# mcu0_primary.net
KiCad netlist of a schematic drawn in Altium Designer
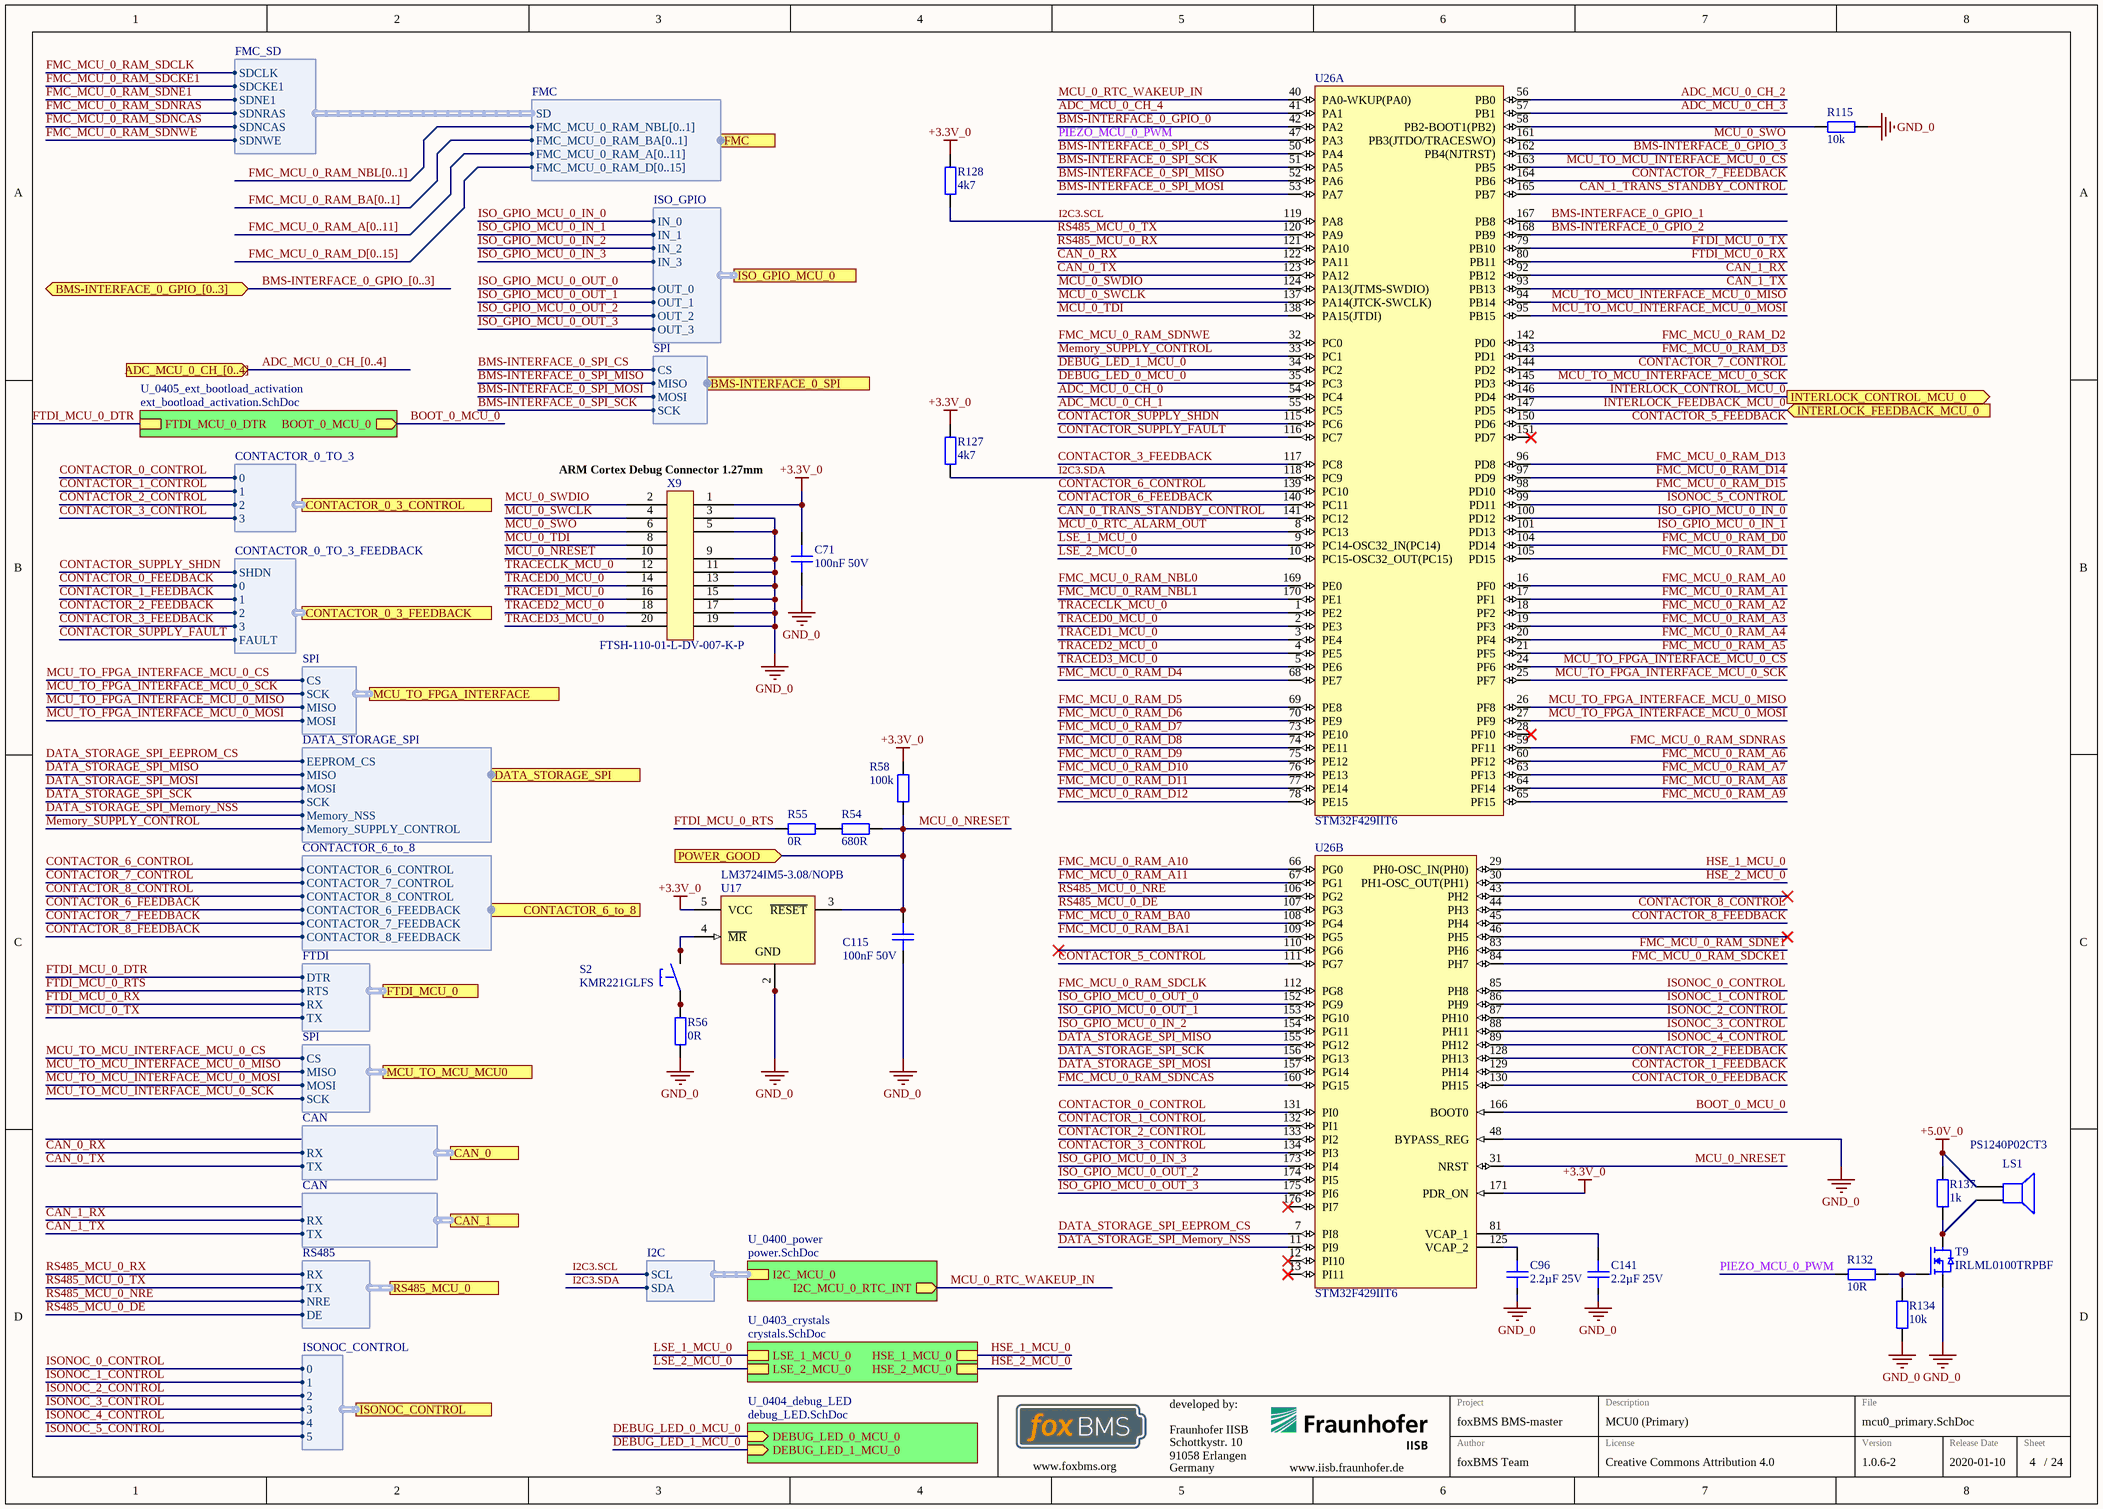
[diagram p0: mcu0_primary.SchDoc]

(export (version "E")
  (design (tool "Eeschema 10.0.6"))
  (components
    (comp (ref "C71")
      (value "100nF 50V")
      (footprint "0603C")
      (description "Ceramic, 100nF, ±10%, 50V, X7R, –55 to 125°C, 0603 (1608),RoHS, Automotive")
      (fields (field (name "PART NUMBER") "GCJ188R71H104KA12") (field (name "TOLERANCE") "±10%"))
      (libsource (lib "master-010106") (part "C"))
    )
    (comp (ref "C96")
      (value "2.2µF 25V")
      (footprint "0805C")
      (description "Ceramic, 2.2µF, ±10%, 25V, X7R, –55 to 125°C, 0805 (2012),RoHS, Automotive")
      (fields (field (name "PART NUMBER") "GCJ21BR71E225KA01") (field (name "TOLERANCE") "±10%"))
      (libsource (lib "master-010106") (part "gen_C_ceramic_2u2_50V_X7R_0805"))
    )
    (comp (ref "C115")
      (value "100nF 50V")
      (footprint "0603C")
      (description "Ceramic, 100nF, ±10%, 50V, X7R, –55 to 125°C, 0603 (1608),RoHS, Automotive")
      (fields (field (name "PART NUMBER") "GCJ188R71H104KA12") (field (name "TOLERANCE") "±10%"))
      (libsource (lib "master-010106") (part "C"))
    )
    (comp (ref "C141")
      (value "2.2µF 25V")
      (footprint "0805C")
      (description "Ceramic, 2.2µF, ±10%, 25V, X7R, –55 to 125°C, 0805 (2012),RoHS, Automotive")
      (fields (field (name "PART NUMBER") "GCJ21BR71E225KA01") (field (name "TOLERANCE") "±10%"))
      (libsource (lib "master-010106") (part "gen_C_ceramic_2u2_50V_X7R_0805"))
    )
    (comp (ref "LS1")
      (value "PS1240P02CT3")
      (footprint "PS12")
      (description "Loudspeaker")
      (libsource (lib "Miscellaneous Devices") (part "Speaker"))
    )
    (comp (ref "R54")
      (value "680R")
      (footprint "0603R")
      (description "SMD Resistor 680R 0603")
      (fields (field (name "PART NUMBER") "gen_R_680R_0603") (field (name "TOLERANCE") "1%"))
      (libsource (lib "master-010106") (part "R"))
    )
    (comp (ref "R55")
      (value "0R")
      (footprint "0603R")
      (description "SMD Resistor 0R 0603")
      (fields (field (name "PART NUMBER") "gen_R_0R_0603") (field (name "POWER") "0.1W"))
      (libsource (lib "master-010106") (part "R"))
    )
    (comp (ref "R56")
      (value "0R")
      (footprint "0603R")
      (description "SMD Resistor 0R 0603")
      (fields (field (name "PART NUMBER") "gen_R_0R_0603") (field (name "POWER") "0.1W"))
      (libsource (lib "master-010106") (part "R"))
    )
    (comp (ref "R58")
      (value "100k")
      (footprint "0603R")
      (description "SMD Resistor 100k 0603")
      (fields (field (name "PART NUMBER") "gen_R_100k_0603"))
      (libsource (lib "master-010106") (part "gen_R_100k_0603"))
    )
    (comp (ref "R115")
      (value "10k")
      (footprint "0603R")
      (description "SMD Resistor 10k 0603")
      (fields (field (name "PART NUMBER") "gen_R_10k_0603") (field (name "TOLERANCE") "1%"))
      (libsource (lib "master-010106") (part "R"))
    )
    (comp (ref "R127")
      (value "4k7")
      (footprint "0603R")
      (description "SMD Resistor 4.7k 0603")
      (fields (field (name "PART NUMBER") "gen_R_4k7_0603"))
      (libsource (lib "master-010106") (part "gen_R_4k7_0603"))
    )
    (comp (ref "R128")
      (value "4k7")
      (footprint "0603R")
      (description "SMD Resistor 4.7k 0603")
      (fields (field (name "PART NUMBER") "gen_R_4k7_0603"))
      (libsource (lib "master-010106") (part "gen_R_4k7_0603"))
    )
    (comp (ref "R132")
      (value "10R")
      (footprint "0603R")
      (description "SMD Resistor 10R 0603")
      (fields (field (name "PART NUMBER") "gen_R_10R_0603") (field (name "TOLERANCE") "1%"))
      (libsource (lib "master-010106") (part "R"))
    )
    (comp (ref "R134")
      (value "10k")
      (footprint "0603R")
      (description "SMD Resistor 10k 0603")
      (fields (field (name "PART NUMBER") "gen_R_10k_0603") (field (name "TOLERANCE") "1%"))
      (libsource (lib "master-010106") (part "R"))
    )
    (comp (ref "R137")
      (value "1k")
      (footprint "0603R")
      (description "SMD Resistor 1k 0603")
      (fields (field (name "PART NUMBER") "gen_R_1k_0603") (field (name "TOLERANCE") "1%"))
      (libsource (lib "master-010106") (part "R"))
    )
    (comp (ref "S2")
      (value "KMR221GLFS")
      (footprint "KMR2_Series")
      (description "Microminiature Tactile Switch")
      (fields (field (name "MANUFACTURER") "CK Components"))
      (libsource (lib "OE750") (part "Switch_4_Pin"))
    )
    (comp (ref "T9")
      (value "IRLML0100TRPBF")
      (footprint "SOT95P237X110-3N")
      (description "MOSFET-Transistor, n-Kanal, 1.6 A, 100 V, 0.178 ohm, 10 V, 2.5 V")
      (fields (field (name "MANUFACTURER") "Infineon"))
      (libsource (lib "OE750") (part "NMOS"))
    )
    (comp (ref "U17")
      (value "LM3724IM5-3.08/NOPB")
      (footprint "MF05A_N")
      (description "5-Pin Microprocessor Reset Circuits, 5-pin SOT-23, Pb-Free")
      (fields (field (name "MANUFACTURER") "National Semiconductor"))
      (libsource (lib "Altium Content Vault") (part "PM-SCCT-LM3724-5"))
    )
    (comp (ref "U26")
      (value "STM32F429IIT6")
      (footprint "STM-LQFP176_N")
      (fields (field (name "MANUFACTURER") "STMicroelectronics"))
      (libsource (lib "ti-import") (part "MC-ARM-STM32F4X9-SQ176"))
    )
    (comp (ref "X9")
      (value "FTSH-110-01-L-DV-007-K-P")
      (footprint "CORTEX_DEBUG_20_PIN")
      (description "Board-To-Board Connector, ARM Cortex Debug Header 20 Pin")
      (fields
        (field (name "PART NUMBER") "samtec_FTSH-110-01-L-DV-007-K-P")
        (field (name "MANUFACTURER") "Samtec")
      )
      (libsource (lib "OE750") (part "CORTEX_DEBUG_20_PIN"))
    )
  )
  (nets
    (net (code "14") (name "+3.3V_0") (class "Default")
      (node (ref "C71") (pin "1") (pinfunction "1_1") (pintype "passive"))
      (node (ref "R127") (pin "2") (pinfunction "2_2") (pintype "passive"))
      (node (ref "R128") (pin "2") (pinfunction "2_2") (pintype "passive"))
      (node (ref "R58") (pin "2") (pinfunction "2_2") (pintype "passive"))
      (node (ref "U17") (pin "5") (pinfunction "VCC_5") (pintype "power_in"))
      (node (ref "U26") (pin "171") (pinfunction "PDR_ON_171") (pintype "input"))
      (node (ref "X9") (pin "1") (pintype "passive"))
    )
    (net (code "15") (name "+5.0V_0") (class "Default")
      (node (ref "LS1") (pin "1") (pinfunction "1_1") (pintype "passive"))
      (node (ref "R137") (pin "2") (pinfunction "2_2") (pintype "passive"))
    )
    (net (code "16") (name "/ADC_MCU_0_CH_0") (class "Default")
      (node (ref "U26") (pin "54") (pinfunction "PC4_54") (pintype "bidirectional"))
    )
    (net (code "17") (name "/ADC_MCU_0_CH_1") (class "Default")
      (node (ref "U26") (pin "55") (pinfunction "PC5_55") (pintype "bidirectional"))
    )
    (net (code "18") (name "/ADC_MCU_0_CH_2") (class "Default")
      (node (ref "U26") (pin "56") (pinfunction "PB0_56") (pintype "bidirectional"))
    )
    (net (code "19") (name "/ADC_MCU_0_CH_3") (class "Default")
      (node (ref "U26") (pin "57") (pinfunction "PB1_57") (pintype "bidirectional"))
    )
    (net (code "20") (name "/ADC_MCU_0_CH_4") (class "Default")
      (node (ref "U26") (pin "41") (pinfunction "PA1_41") (pintype "bidirectional"))
    )
    (net (code "22") (name "/BMS-INTERFACE_0_GPIO_0") (class "Default")
      (node (ref "U26") (pin "42") (pinfunction "PA2_42") (pintype "bidirectional"))
    )
    (net (code "23") (name "/BMS-INTERFACE_0_GPIO_1") (class "Default")
      (node (ref "U26") (pin "167") (pinfunction "PB8_167") (pintype "bidirectional"))
    )
    (net (code "24") (name "/BMS-INTERFACE_0_GPIO_2") (class "Default")
      (node (ref "U26") (pin "168") (pinfunction "PB9_168") (pintype "bidirectional"))
    )
    (net (code "25") (name "/BMS-INTERFACE_0_GPIO_3") (class "Default")
      (node (ref "U26") (pin "162") (pinfunction "PB4(NJTRST)_162") (pintype "bidirectional"))
    )
    (net (code "27") (name "/BMS-INTERFACE_0_SPI_CS") (class "Default")
      (node (ref "U26") (pin "50") (pinfunction "PA4_50") (pintype "bidirectional"))
    )
    (net (code "28") (name "/BMS-INTERFACE_0_SPI_MISO") (class "Default")
      (node (ref "U26") (pin "52") (pinfunction "PA6_52") (pintype "bidirectional"))
    )
    (net (code "29") (name "/BMS-INTERFACE_0_SPI_MOSI") (class "Default")
      (node (ref "U26") (pin "53") (pinfunction "PA7_53") (pintype "bidirectional"))
    )
    (net (code "30") (name "/BMS-INTERFACE_0_SPI_SCK") (class "Default")
      (node (ref "U26") (pin "51") (pinfunction "PA5_51") (pintype "bidirectional"))
    )
    (net (code "31") (name "/BOOT_0_MCU_0") (class "Default")
      (node (ref "U26") (pin "166") (pinfunction "BOOT0_166") (pintype "input"))
    )
    (net (code "32") (name "/CAN_0_RX") (class "Default")
      (node (ref "U26") (pin "122") (pinfunction "PA11_122") (pintype "bidirectional"))
    )
    (net (code "33") (name "/CAN_0_TRANS_STANDBY_CONTROL") (class "Default")
      (node (ref "U26") (pin "141") (pinfunction "PC12_141") (pintype "bidirectional"))
    )
    (net (code "34") (name "/CAN_0_TX") (class "Default")
      (node (ref "U26") (pin "123") (pinfunction "PA12_123") (pintype "bidirectional"))
    )
    (net (code "35") (name "/CAN_1_RX") (class "Default")
      (node (ref "U26") (pin "92") (pinfunction "PB12_92") (pintype "bidirectional"))
    )
    (net (code "36") (name "/CAN_1_TRANS_STANDBY_CONTROL") (class "Default")
      (node (ref "U26") (pin "165") (pinfunction "PB7_165") (pintype "bidirectional"))
    )
    (net (code "37") (name "/CAN_1_TX") (class "Default")
      (node (ref "U26") (pin "93") (pinfunction "PB13_93") (pintype "bidirectional"))
    )
    (net (code "38") (name "/CONTACTOR_0_CONTROL") (class "Default")
      (node (ref "U26") (pin "131") (pinfunction "PI0_131") (pintype "bidirectional"))
    )
    (net (code "39") (name "/CONTACTOR_0_FEEDBACK") (class "Default")
      (node (ref "U26") (pin "130") (pinfunction "PH15_130") (pintype "bidirectional"))
    )
    (net (code "40") (name "/CONTACTOR_1_CONTROL") (class "Default")
      (node (ref "U26") (pin "132") (pinfunction "PI1_132") (pintype "bidirectional"))
    )
    (net (code "41") (name "/CONTACTOR_1_FEEDBACK") (class "Default")
      (node (ref "U26") (pin "129") (pinfunction "PH14_129") (pintype "bidirectional"))
    )
    (net (code "42") (name "/CONTACTOR_2_CONTROL") (class "Default")
      (node (ref "U26") (pin "133") (pinfunction "PI2_133") (pintype "bidirectional"))
    )
    (net (code "43") (name "/CONTACTOR_2_FEEDBACK") (class "Default")
      (node (ref "U26") (pin "128") (pinfunction "PH13_128") (pintype "bidirectional"))
    )
    (net (code "44") (name "/CONTACTOR_3_CONTROL") (class "Default")
      (node (ref "U26") (pin "134") (pinfunction "PI3_134") (pintype "bidirectional"))
    )
    (net (code "45") (name "/CONTACTOR_3_FEEDBACK") (class "Default")
      (node (ref "U26") (pin "117") (pinfunction "PC8_117") (pintype "bidirectional"))
    )
    (net (code "46") (name "/CONTACTOR_5_CONTROL") (class "Default")
      (node (ref "U26") (pin "111") (pinfunction "PG7_111") (pintype "bidirectional"))
    )
    (net (code "47") (name "/CONTACTOR_5_FEEDBACK") (class "Default")
      (node (ref "U26") (pin "150") (pinfunction "PD6_150") (pintype "bidirectional"))
    )
    (net (code "48") (name "/CONTACTOR_6_CONTROL") (class "Default")
      (node (ref "U26") (pin "139") (pinfunction "PC10_139") (pintype "bidirectional"))
    )
    (net (code "49") (name "/CONTACTOR_6_FEEDBACK") (class "Default")
      (node (ref "U26") (pin "140") (pinfunction "PC11_140") (pintype "bidirectional"))
    )
    (net (code "50") (name "/CONTACTOR_7_CONTROL") (class "Default")
      (node (ref "U26") (pin "144") (pinfunction "PD2_144") (pintype "bidirectional"))
    )
    (net (code "51") (name "/CONTACTOR_7_FEEDBACK") (class "Default")
      (node (ref "U26") (pin "164") (pinfunction "PB6_164") (pintype "bidirectional"))
    )
    (net (code "52") (name "/CONTACTOR_8_CONTROL") (class "Default")
      (node (ref "U26") (pin "44") (pinfunction "PH3_44") (pintype "bidirectional"))
    )
    (net (code "53") (name "/CONTACTOR_8_FEEDBACK") (class "Default")
      (node (ref "U26") (pin "45") (pinfunction "PH4_45") (pintype "bidirectional"))
    )
    (net (code "54") (name "/CONTACTOR_SUPPLY_FAULT") (class "Default")
      (node (ref "U26") (pin "116") (pinfunction "PC7_116") (pintype "bidirectional"))
    )
    (net (code "55") (name "/CONTACTOR_SUPPLY_SHDN") (class "Default")
      (node (ref "U26") (pin "115") (pinfunction "PC6_115") (pintype "bidirectional"))
    )
    (net (code "56") (name "/DATA_STORAGE_SPI_EEPROM_CS") (class "Default")
      (node (ref "U26") (pin "7") (pinfunction "PI8_7") (pintype "bidirectional"))
    )
    (net (code "57") (name "/DATA_STORAGE_SPI_MISO") (class "Default")
      (node (ref "U26") (pin "155") (pinfunction "PG12_155") (pintype "bidirectional"))
    )
    (net (code "58") (name "/DATA_STORAGE_SPI_MOSI") (class "Default")
      (node (ref "U26") (pin "157") (pinfunction "PG14_157") (pintype "bidirectional"))
    )
    (net (code "59") (name "/DATA_STORAGE_SPI_Memory_NSS") (class "Default")
      (node (ref "U26") (pin "11") (pinfunction "PI9_11") (pintype "bidirectional"))
    )
    (net (code "60") (name "/DATA_STORAGE_SPI_SCK") (class "Default")
      (node (ref "U26") (pin "156") (pinfunction "PG13_156") (pintype "bidirectional"))
    )
    (net (code "61") (name "/DEBUG_LED_0_MCU_0") (class "Default")
      (node (ref "U26") (pin "35") (pinfunction "PC3_35") (pintype "bidirectional"))
    )
    (net (code "62") (name "/DEBUG_LED_1_MCU_0") (class "Default")
      (node (ref "U26") (pin "34") (pinfunction "PC2_34") (pintype "bidirectional"))
    )
    (net (code "63") (name "/FMC_MCU_0_RAM_A0") (class "Default")
      (node (ref "U26") (pin "16") (pinfunction "PF0_16") (pintype "bidirectional"))
    )
    (net (code "64") (name "/FMC_MCU_0_RAM_A1") (class "Default")
      (node (ref "U26") (pin "17") (pinfunction "PF1_17") (pintype "bidirectional"))
    )
    (net (code "65") (name "/FMC_MCU_0_RAM_A2") (class "Default")
      (node (ref "U26") (pin "18") (pinfunction "PF2_18") (pintype "bidirectional"))
    )
    (net (code "66") (name "/FMC_MCU_0_RAM_A3") (class "Default")
      (node (ref "U26") (pin "19") (pinfunction "PF3_19") (pintype "bidirectional"))
    )
    (net (code "67") (name "/FMC_MCU_0_RAM_A4") (class "Default")
      (node (ref "U26") (pin "20") (pinfunction "PF4_20") (pintype "bidirectional"))
    )
    (net (code "68") (name "/FMC_MCU_0_RAM_A5") (class "Default")
      (node (ref "U26") (pin "21") (pinfunction "PF5_21") (pintype "bidirectional"))
    )
    (net (code "69") (name "/FMC_MCU_0_RAM_A6") (class "Default")
      (node (ref "U26") (pin "60") (pinfunction "PF12_60") (pintype "bidirectional"))
    )
    (net (code "70") (name "/FMC_MCU_0_RAM_A7") (class "Default")
      (node (ref "U26") (pin "63") (pinfunction "PF13_63") (pintype "bidirectional"))
    )
    (net (code "71") (name "/FMC_MCU_0_RAM_A8") (class "Default")
      (node (ref "U26") (pin "64") (pinfunction "PF14_64") (pintype "bidirectional"))
    )
    (net (code "72") (name "/FMC_MCU_0_RAM_A9") (class "Default")
      (node (ref "U26") (pin "65") (pinfunction "PF15_65") (pintype "bidirectional"))
    )
    (net (code "73") (name "/FMC_MCU_0_RAM_A10") (class "Default")
      (node (ref "U26") (pin "66") (pinfunction "PG0_66") (pintype "bidirectional"))
    )
    (net (code "74") (name "/FMC_MCU_0_RAM_A11") (class "Default")
      (node (ref "U26") (pin "67") (pinfunction "PG1_67") (pintype "bidirectional"))
    )
    (net (code "76") (name "/FMC_MCU_0_RAM_BA0") (class "Default")
      (node (ref "U26") (pin "108") (pinfunction "PG4_108") (pintype "bidirectional"))
    )
    (net (code "77") (name "/FMC_MCU_0_RAM_BA1") (class "Default")
      (node (ref "U26") (pin "109") (pinfunction "PG5_109") (pintype "bidirectional"))
    )
    (net (code "79") (name "/FMC_MCU_0_RAM_D0") (class "Default")
      (node (ref "U26") (pin "104") (pinfunction "PD14_104") (pintype "bidirectional"))
    )
    (net (code "80") (name "/FMC_MCU_0_RAM_D1") (class "Default")
      (node (ref "U26") (pin "105") (pinfunction "PD15_105") (pintype "bidirectional"))
    )
    (net (code "81") (name "/FMC_MCU_0_RAM_D2") (class "Default")
      (node (ref "U26") (pin "142") (pinfunction "PD0_142") (pintype "bidirectional"))
    )
    (net (code "82") (name "/FMC_MCU_0_RAM_D3") (class "Default")
      (node (ref "U26") (pin "143") (pinfunction "PD1_143") (pintype "bidirectional"))
    )
    (net (code "83") (name "/FMC_MCU_0_RAM_D4") (class "Default")
      (node (ref "U26") (pin "68") (pinfunction "PE7_68") (pintype "bidirectional"))
    )
    (net (code "84") (name "/FMC_MCU_0_RAM_D5") (class "Default")
      (node (ref "U26") (pin "69") (pinfunction "PE8_69") (pintype "bidirectional"))
    )
    (net (code "85") (name "/FMC_MCU_0_RAM_D6") (class "Default")
      (node (ref "U26") (pin "70") (pinfunction "PE9_70") (pintype "bidirectional"))
    )
    (net (code "86") (name "/FMC_MCU_0_RAM_D7") (class "Default")
      (node (ref "U26") (pin "73") (pinfunction "PE10_73") (pintype "bidirectional"))
    )
    (net (code "87") (name "/FMC_MCU_0_RAM_D8") (class "Default")
      (node (ref "U26") (pin "74") (pinfunction "PE11_74") (pintype "bidirectional"))
    )
    (net (code "88") (name "/FMC_MCU_0_RAM_D9") (class "Default")
      (node (ref "U26") (pin "75") (pinfunction "PE12_75") (pintype "bidirectional"))
    )
    (net (code "89") (name "/FMC_MCU_0_RAM_D10") (class "Default")
      (node (ref "U26") (pin "76") (pinfunction "PE13_76") (pintype "bidirectional"))
    )
    (net (code "90") (name "/FMC_MCU_0_RAM_D11") (class "Default")
      (node (ref "U26") (pin "77") (pinfunction "PE14_77") (pintype "bidirectional"))
    )
    (net (code "91") (name "/FMC_MCU_0_RAM_D12") (class "Default")
      (node (ref "U26") (pin "78") (pinfunction "PE15_78") (pintype "bidirectional"))
    )
    (net (code "92") (name "/FMC_MCU_0_RAM_D13") (class "Default")
      (node (ref "U26") (pin "96") (pinfunction "PD8_96") (pintype "bidirectional"))
    )
    (net (code "93") (name "/FMC_MCU_0_RAM_D14") (class "Default")
      (node (ref "U26") (pin "97") (pinfunction "PD9_97") (pintype "bidirectional"))
    )
    (net (code "94") (name "/FMC_MCU_0_RAM_D15") (class "Default")
      (node (ref "U26") (pin "98") (pinfunction "PD10_98") (pintype "bidirectional"))
    )
    (net (code "96") (name "/FMC_MCU_0_RAM_NBL0") (class "Default")
      (node (ref "U26") (pin "169") (pinfunction "PE0_169") (pintype "bidirectional"))
    )
    (net (code "97") (name "/FMC_MCU_0_RAM_NBL1") (class "Default")
      (node (ref "U26") (pin "170") (pinfunction "PE1_170") (pintype "bidirectional"))
    )
    (net (code "99") (name "/FMC_MCU_0_RAM_SDCKE1") (class "Default")
      (node (ref "U26") (pin "84") (pinfunction "PH7_84") (pintype "bidirectional"))
    )
    (net (code "100") (name "/FMC_MCU_0_RAM_SDCLK") (class "Default")
      (node (ref "U26") (pin "112") (pinfunction "PG8_112") (pintype "bidirectional"))
    )
    (net (code "101") (name "/FMC_MCU_0_RAM_SDNCAS") (class "Default")
      (node (ref "U26") (pin "160") (pinfunction "PG15_160") (pintype "bidirectional"))
    )
    (net (code "102") (name "/FMC_MCU_0_RAM_SDNE1") (class "Default")
      (node (ref "U26") (pin "83") (pinfunction "PH6_83") (pintype "bidirectional"))
    )
    (net (code "103") (name "/FMC_MCU_0_RAM_SDNRAS") (class "Default")
      (node (ref "U26") (pin "59") (pinfunction "PF11_59") (pintype "bidirectional"))
    )
    (net (code "104") (name "/FMC_MCU_0_RAM_SDNWE") (class "Default")
      (node (ref "U26") (pin "32") (pinfunction "PC0_32") (pintype "bidirectional"))
    )
    (net (code "107") (name "/FTDI_MCU_0_RTS") (class "Default")
      (node (ref "R55") (pin "2") (pinfunction "2_2") (pintype "passive"))
    )
    (net (code "108") (name "/FTDI_MCU_0_RX") (class "Default")
      (node (ref "U26") (pin "80") (pinfunction "PB11_80") (pintype "bidirectional"))
    )
    (net (code "109") (name "/FTDI_MCU_0_TX") (class "Default")
      (node (ref "U26") (pin "79") (pinfunction "PB10_79") (pintype "bidirectional"))
    )
    (net (code "110") (name "/HSE_1_MCU_0") (class "Default")
      (node (ref "U26") (pin "29") (pinfunction "PH0-OSC_IN(PH0)_29") (pintype "bidirectional"))
    )
    (net (code "111") (name "/HSE_2_MCU_0") (class "Default")
      (node (ref "U26") (pin "30") (pinfunction "PH1-OSC_OUT(PH1)_30") (pintype "bidirectional"))
    )
    (net (code "112") (name "/I2C3.SCL") (class "Default")
      (node (ref "R128") (pin "1") (pinfunction "1_1") (pintype "passive"))
      (node (ref "U26") (pin "119") (pinfunction "PA8_119") (pintype "bidirectional"))
    )
    (net (code "113") (name "/I2C3.SDA") (class "Default")
      (node (ref "R127") (pin "1") (pinfunction "1_1") (pintype "passive"))
      (node (ref "U26") (pin "118") (pinfunction "PC9_118") (pintype "bidirectional"))
    )
    (net (code "114") (name "/INTERLOCK_CONTROL_MCU_0") (class "Default")
      (node (ref "U26") (pin "146") (pinfunction "PD4_146") (pintype "bidirectional"))
    )
    (net (code "115") (name "/INTERLOCK_FEEDBACK_MCU_0") (class "Default")
      (node (ref "U26") (pin "147") (pinfunction "PD5_147") (pintype "bidirectional"))
    )
    (net (code "116") (name "/ISONOC_0_CONTROL") (class "Default")
      (node (ref "U26") (pin "85") (pinfunction "PH8_85") (pintype "bidirectional"))
    )
    (net (code "117") (name "/ISONOC_1_CONTROL") (class "Default")
      (node (ref "U26") (pin "86") (pinfunction "PH9_86") (pintype "bidirectional"))
    )
    (net (code "118") (name "/ISONOC_2_CONTROL") (class "Default")
      (node (ref "U26") (pin "87") (pinfunction "PH10_87") (pintype "bidirectional"))
    )
    (net (code "119") (name "/ISONOC_3_CONTROL") (class "Default")
      (node (ref "U26") (pin "88") (pinfunction "PH11_88") (pintype "bidirectional"))
    )
    (net (code "120") (name "/ISONOC_4_CONTROL") (class "Default")
      (node (ref "U26") (pin "89") (pinfunction "PH12_89") (pintype "bidirectional"))
    )
    (net (code "121") (name "/ISONOC_5_CONTROL") (class "Default")
      (node (ref "U26") (pin "99") (pinfunction "PD11_99") (pintype "bidirectional"))
    )
    (net (code "122") (name "/ISO_GPIO_MCU_0_IN_0") (class "Default")
      (node (ref "U26") (pin "100") (pinfunction "PD12_100") (pintype "bidirectional"))
    )
    (net (code "123") (name "/ISO_GPIO_MCU_0_IN_1") (class "Default")
      (node (ref "U26") (pin "101") (pinfunction "PD13_101") (pintype "bidirectional"))
    )
    (net (code "124") (name "/ISO_GPIO_MCU_0_IN_2") (class "Default")
      (node (ref "U26") (pin "154") (pinfunction "PG11_154") (pintype "bidirectional"))
    )
    (net (code "125") (name "/ISO_GPIO_MCU_0_IN_3") (class "Default")
      (node (ref "U26") (pin "173") (pinfunction "PI4_173") (pintype "bidirectional"))
    )
    (net (code "126") (name "/ISO_GPIO_MCU_0_OUT_0") (class "Default")
      (node (ref "U26") (pin "152") (pinfunction "PG9_152") (pintype "bidirectional"))
    )
    (net (code "127") (name "/ISO_GPIO_MCU_0_OUT_1") (class "Default")
      (node (ref "U26") (pin "153") (pinfunction "PG10_153") (pintype "bidirectional"))
    )
    (net (code "128") (name "/ISO_GPIO_MCU_0_OUT_2") (class "Default")
      (node (ref "U26") (pin "174") (pinfunction "PI5_174") (pintype "bidirectional"))
    )
    (net (code "129") (name "/ISO_GPIO_MCU_0_OUT_3") (class "Default")
      (node (ref "U26") (pin "175") (pinfunction "PI6_175") (pintype "bidirectional"))
    )
    (net (code "130") (name "/LSE_1_MCU_0") (class "Default")
      (node (ref "U26") (pin "9") (pinfunction "PC14-OSC32_IN(PC14)_9") (pintype "bidirectional"))
    )
    (net (code "131") (name "/LSE_2_MCU_0") (class "Default")
      (node (ref "U26") (pin "10") (pinfunction "PC15-OSC32_OUT(PC15)_10") (pintype "bidirectional"))
    )
    (net (code "132") (name "/MCU_0_NRESET") (class "Default")
      (node (ref "C115") (pin "1") (pinfunction "1_1") (pintype "passive"))
      (node (ref "R54") (pin "1") (pinfunction "1_1") (pintype "passive"))
      (node (ref "R58") (pin "1") (pinfunction "1_1") (pintype "passive"))
      (node (ref "U17") (pin "3") (pinfunction "~{RESET}_3") (pintype "open_collector"))
      (node (ref "U26") (pin "31") (pinfunction "NRST_31") (pintype "bidirectional"))
      (node (ref "X9") (pin "10") (pintype "passive"))
    )
    (net (code "133") (name "/MCU_0_RTC_ALARM_OUT") (class "Default")
      (node (ref "U26") (pin "8") (pinfunction "PC13_8") (pintype "bidirectional"))
    )
    (net (code "134") (name "/MCU_0_RTC_WAKEUP_IN") (class "Default")
      (node (ref "U26") (pin "40") (pinfunction "PA0-WKUP(PA0)_40") (pintype "bidirectional"))
    )
    (net (code "135") (name "/MCU_0_SWCLK") (class "Default")
      (node (ref "U26") (pin "137") (pinfunction "PA14(JTCK-SWCLK)_137") (pintype "bidirectional"))
      (node (ref "X9") (pin "4") (pintype "passive"))
    )
    (net (code "136") (name "/MCU_0_SWDIO") (class "Default")
      (node (ref "U26") (pin "124") (pinfunction "PA13(JTMS-SWDIO)_124") (pintype "bidirectional"))
      (node (ref "X9") (pin "2") (pintype "passive"))
    )
    (net (code "137") (name "/MCU_0_SWO") (class "Default")
      (node (ref "U26") (pin "161") (pinfunction "PB3(JTDO/TRACESWO)_161") (pintype "bidirectional"))
      (node (ref "X9") (pin "6") (pintype "passive"))
    )
    (net (code "138") (name "/MCU_0_TDI") (class "Default")
      (node (ref "U26") (pin "138") (pinfunction "PA15(JTDI)_138") (pintype "bidirectional"))
      (node (ref "X9") (pin "8") (pintype "passive"))
    )
    (net (code "139") (name "/MCU_TO_FPGA_INTERFACE_MCU_0_CS") (class "Default")
      (node (ref "U26") (pin "24") (pinfunction "PF6_24") (pintype "bidirectional"))
    )
    (net (code "140") (name "/MCU_TO_FPGA_INTERFACE_MCU_0_MISO") (class "Default")
      (node (ref "U26") (pin "26") (pinfunction "PF8_26") (pintype "bidirectional"))
    )
    (net (code "141") (name "/MCU_TO_FPGA_INTERFACE_MCU_0_MOSI") (class "Default")
      (node (ref "U26") (pin "27") (pinfunction "PF9_27") (pintype "bidirectional"))
    )
    (net (code "142") (name "/MCU_TO_FPGA_INTERFACE_MCU_0_SCK") (class "Default")
      (node (ref "U26") (pin "25") (pinfunction "PF7_25") (pintype "bidirectional"))
    )
    (net (code "143") (name "/MCU_TO_MCU_INTERFACE_MCU_0_CS") (class "Default")
      (node (ref "U26") (pin "163") (pinfunction "PB5_163") (pintype "bidirectional"))
    )
    (net (code "144") (name "/MCU_TO_MCU_INTERFACE_MCU_0_MISO") (class "Default")
      (node (ref "U26") (pin "94") (pinfunction "PB14_94") (pintype "bidirectional"))
    )
    (net (code "145") (name "/MCU_TO_MCU_INTERFACE_MCU_0_MOSI") (class "Default")
      (node (ref "U26") (pin "95") (pinfunction "PB15_95") (pintype "bidirectional"))
    )
    (net (code "146") (name "/MCU_TO_MCU_INTERFACE_MCU_0_SCK") (class "Default")
      (node (ref "U26") (pin "145") (pinfunction "PD3_145") (pintype "bidirectional"))
    )
    (net (code "147") (name "/Memory_SUPPLY_CONTROL") (class "Default")
      (node (ref "U26") (pin "33") (pinfunction "PC1_33") (pintype "bidirectional"))
    )
    (net (code "148") (name "/PIEZO_MCU_0_PWM") (class "Default")
      (node (ref "R132") (pin "2") (pinfunction "2_2") (pintype "passive"))
      (node (ref "U26") (pin "47") (pinfunction "PA3_47") (pintype "bidirectional"))
    )
    (net (code "149") (name "/RS485_MCU_0_DE") (class "Default")
      (node (ref "U26") (pin "107") (pinfunction "PG3_107") (pintype "bidirectional"))
    )
    (net (code "150") (name "/RS485_MCU_0_NRE") (class "Default")
      (node (ref "U26") (pin "106") (pinfunction "PG2_106") (pintype "bidirectional"))
    )
    (net (code "151") (name "/RS485_MCU_0_RX") (class "Default")
      (node (ref "U26") (pin "121") (pinfunction "PA10_121") (pintype "bidirectional"))
    )
    (net (code "152") (name "/RS485_MCU_0_TX") (class "Default")
      (node (ref "U26") (pin "120") (pinfunction "PA9_120") (pintype "bidirectional"))
    )
    (net (code "153") (name "/TRACECLK_MCU_0") (class "Default")
      (node (ref "U26") (pin "1") (pinfunction "PE2_1") (pintype "bidirectional"))
      (node (ref "X9") (pin "12") (pintype "passive"))
    )
    (net (code "154") (name "/TRACED0_MCU_0") (class "Default")
      (node (ref "U26") (pin "2") (pinfunction "PE3_2") (pintype "bidirectional"))
      (node (ref "X9") (pin "14") (pintype "passive"))
    )
    (net (code "155") (name "/TRACED1_MCU_0") (class "Default")
      (node (ref "U26") (pin "3") (pinfunction "PE4_3") (pintype "bidirectional"))
      (node (ref "X9") (pin "16") (pintype "passive"))
    )
    (net (code "156") (name "/TRACED2_MCU_0") (class "Default")
      (node (ref "U26") (pin "4") (pinfunction "PE5_4") (pintype "bidirectional"))
      (node (ref "X9") (pin "18") (pintype "passive"))
    )
    (net (code "157") (name "/TRACED3_MCU_0") (class "Default")
      (node (ref "U26") (pin "5") (pinfunction "PE6_5") (pintype "bidirectional"))
      (node (ref "X9") (pin "20") (pintype "passive"))
    )
    (net (code "170") (name "GND_0") (class "Default")
      (node (ref "C115") (pin "2") (pinfunction "2_2") (pintype "passive"))
      (node (ref "C141") (pin "2") (pinfunction "2_2") (pintype "passive"))
      (node (ref "C71") (pin "2") (pinfunction "2_2") (pintype "passive"))
      (node (ref "C96") (pin "2") (pinfunction "2_2") (pintype "passive"))
      (node (ref "R115") (pin "1") (pinfunction "1_1") (pintype "passive"))
      (node (ref "R134") (pin "1") (pinfunction "1_1") (pintype "passive"))
      (node (ref "R56") (pin "1") (pinfunction "1_1") (pintype "passive"))
      (node (ref "T9") (pin "S") (pinfunction "S_S") (pintype "passive"))
      (node (ref "U17") (pin "1") (pinfunction "GND_1") (pintype "power_in"))
      (node (ref "U17") (pin "2") (pinfunction "GND_2") (pintype "power_in"))
      (node (ref "U26") (pin "48") (pinfunction "BYPASS_REG_48") (pintype "input"))
      (node (ref "X9") (pin "11") (pintype "passive"))
      (node (ref "X9") (pin "13") (pintype "passive"))
      (node (ref "X9") (pin "15") (pintype "passive"))
      (node (ref "X9") (pin "17") (pintype "passive"))
      (node (ref "X9") (pin "19") (pintype "passive"))
      (node (ref "X9") (pin "3") (pintype "passive"))
      (node (ref "X9") (pin "5") (pintype "passive"))
      (node (ref "X9") (pin "9") (pintype "passive"))
    )
    (net (code "171") (name "Net-(LS1-Pad2)") (class "Default")
      (node (ref "LS1") (pin "2") (pinfunction "2_2") (pintype "passive"))
      (node (ref "R137") (pin "1") (pinfunction "1_1") (pintype "passive"))
      (node (ref "T9") (pin "D") (pinfunction "D_D") (pintype "passive"))
    )
    (net (code "172") (name "Net-(R54-Pad2)") (class "Default")
      (node (ref "R54") (pin "2") (pinfunction "2_2") (pintype "passive"))
      (node (ref "R55") (pin "1") (pinfunction "1_1") (pintype "passive"))
    )
    (net (code "173") (name "Net-(R56-Pad2)") (class "Default")
      (node (ref "R56") (pin "2") (pinfunction "2_2") (pintype "passive"))
      (node (ref "S2") (pin "1") (pintype "passive"))
      (node (ref "S2") (pin "2") (pintype "passive"))
    )
    (net (code "174") (name "Net-(R132-Pad1)") (class "Default")
      (node (ref "R132") (pin "1") (pinfunction "1_1") (pintype "passive"))
      (node (ref "R134") (pin "2") (pinfunction "2_2") (pintype "passive"))
      (node (ref "T9") (pin "G") (pinfunction "G_G") (pintype "passive"))
    )
    (net (code "175") (name "Net-(U17-~{MR})") (class "Default")
      (node (ref "S2") (pin "3") (pintype "passive"))
      (node (ref "S2") (pin "4") (pintype "passive"))
      (node (ref "U17") (pin "4") (pinfunction "~{MR}_4") (pintype "input"))
    )
    (net (code "176") (name "Net-(U26A-PB2-BOOT1(PB2))") (class "Default")
      (node (ref "R115") (pin "2") (pinfunction "2_2") (pintype "passive"))
      (node (ref "U26") (pin "58") (pinfunction "PB2-BOOT1(PB2)_58") (pintype "bidirectional"))
    )
    (net (code "177") (name "Net-(U26B-VCAP_1)") (class "Default")
      (node (ref "C141") (pin "1") (pinfunction "1_1") (pintype "passive"))
      (node (ref "U26") (pin "81") (pinfunction "VCAP_1_81") (pintype "power_in"))
    )
    (net (code "178") (name "Net-(U26B-VCAP_2)") (class "Default")
      (node (ref "C96") (pin "1") (pinfunction "1_1") (pintype "passive"))
      (node (ref "U26") (pin "125") (pinfunction "VCAP_2_125") (pintype "power_in"))
    )
    (net (code "179") (name "unconnected-(U26A-PD7-Pad151)") (class "Default")
      (node (ref "U26") (pin "151") (pinfunction "PD7_151") (pintype "bidirectional+no_connect"))
    )
    (net (code "180") (name "unconnected-(U26A-PF10-Pad28)") (class "Default")
      (node (ref "U26") (pin "28") (pinfunction "PF10_28") (pintype "bidirectional+no_connect"))
    )
    (net (code "181") (name "unconnected-(U26B-PG6-Pad110)") (class "Default")
      (node (ref "U26") (pin "110") (pinfunction "PG6_110") (pintype "bidirectional+no_connect"))
    )
    (net (code "182") (name "unconnected-(U26B-PH2-Pad43)") (class "Default")
      (node (ref "U26") (pin "43") (pinfunction "PH2_43") (pintype "bidirectional+no_connect"))
    )
    (net (code "183") (name "unconnected-(U26B-PH5-Pad46)") (class "Default")
      (node (ref "U26") (pin "46") (pinfunction "PH5_46") (pintype "bidirectional+no_connect"))
    )
    (net (code "184") (name "unconnected-(U26B-PI7-Pad176)") (class "Default")
      (node (ref "U26") (pin "176") (pinfunction "PI7_176") (pintype "bidirectional+no_connect"))
    )
    (net (code "185") (name "unconnected-(U26B-PI10-Pad12)") (class "Default")
      (node (ref "U26") (pin "12") (pinfunction "PI10_12") (pintype "bidirectional+no_connect"))
    )
    (net (code "186") (name "unconnected-(U26B-PI11-Pad13)") (class "Default")
      (node (ref "U26") (pin "13") (pinfunction "PI11_13") (pintype "bidirectional+no_connect"))
    )
  )
)
